# clock.net
KiCad netlist of a schematic drawn in EAGLE
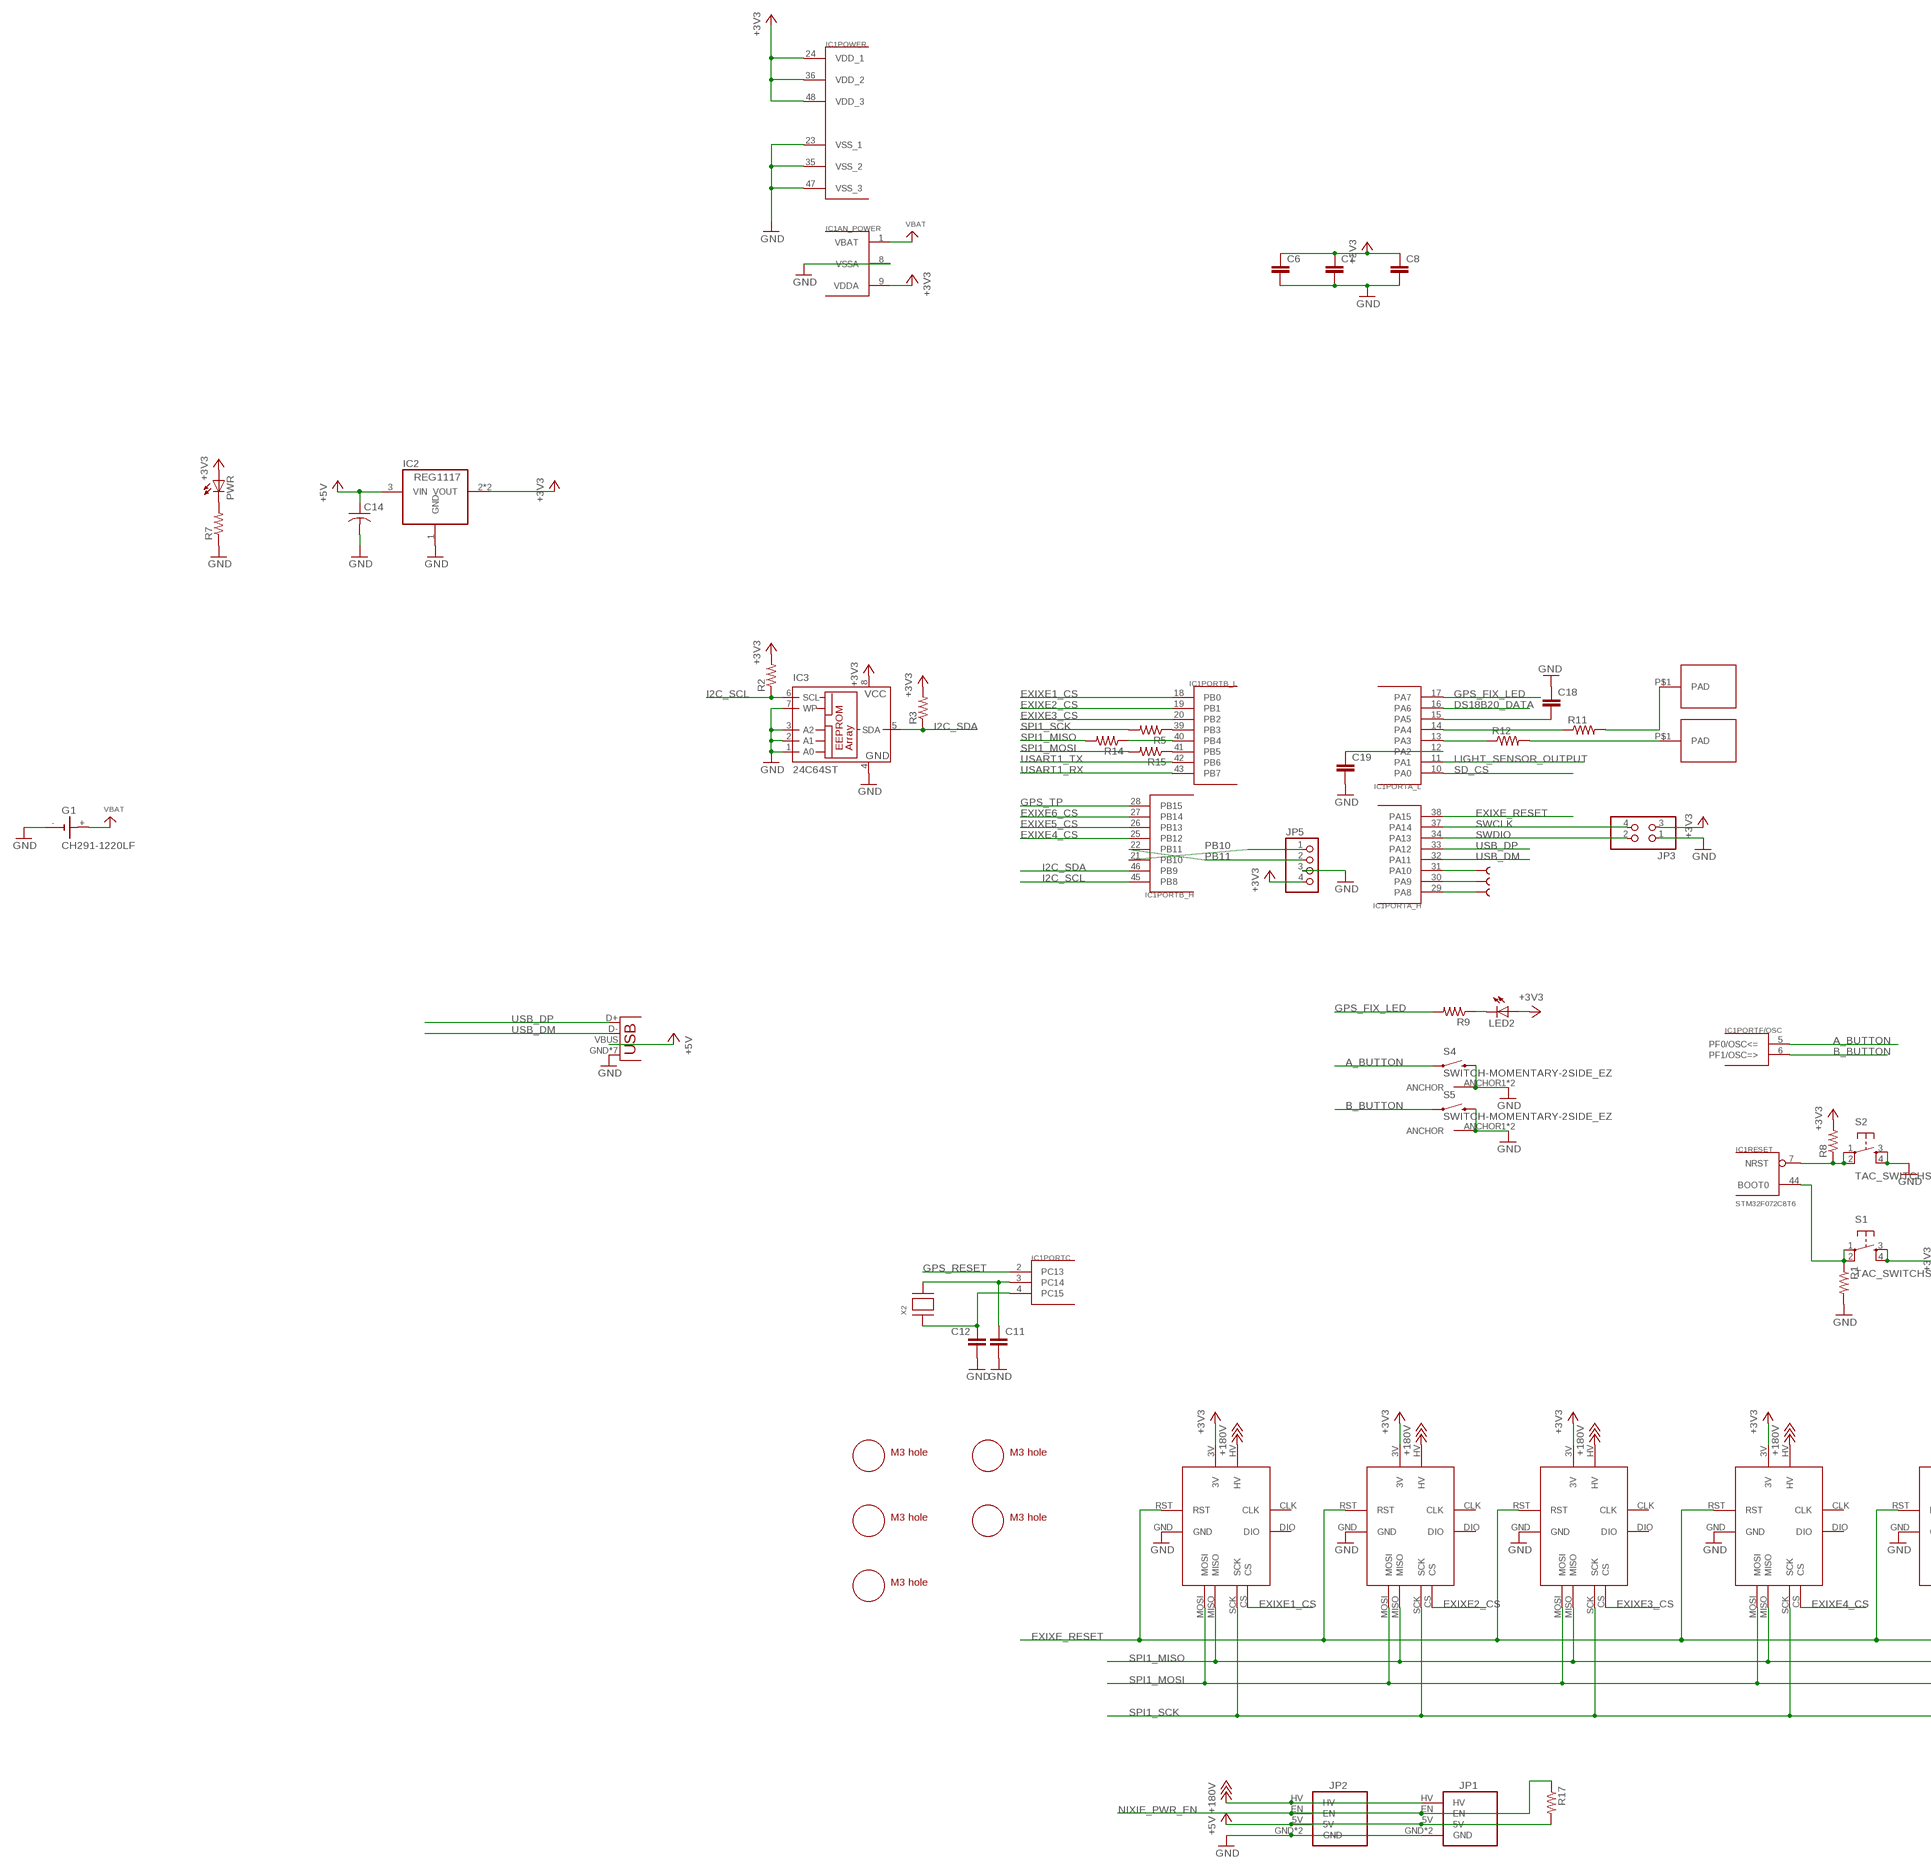
[diagram p0: schematic, sheet 1, part 1 of 2]
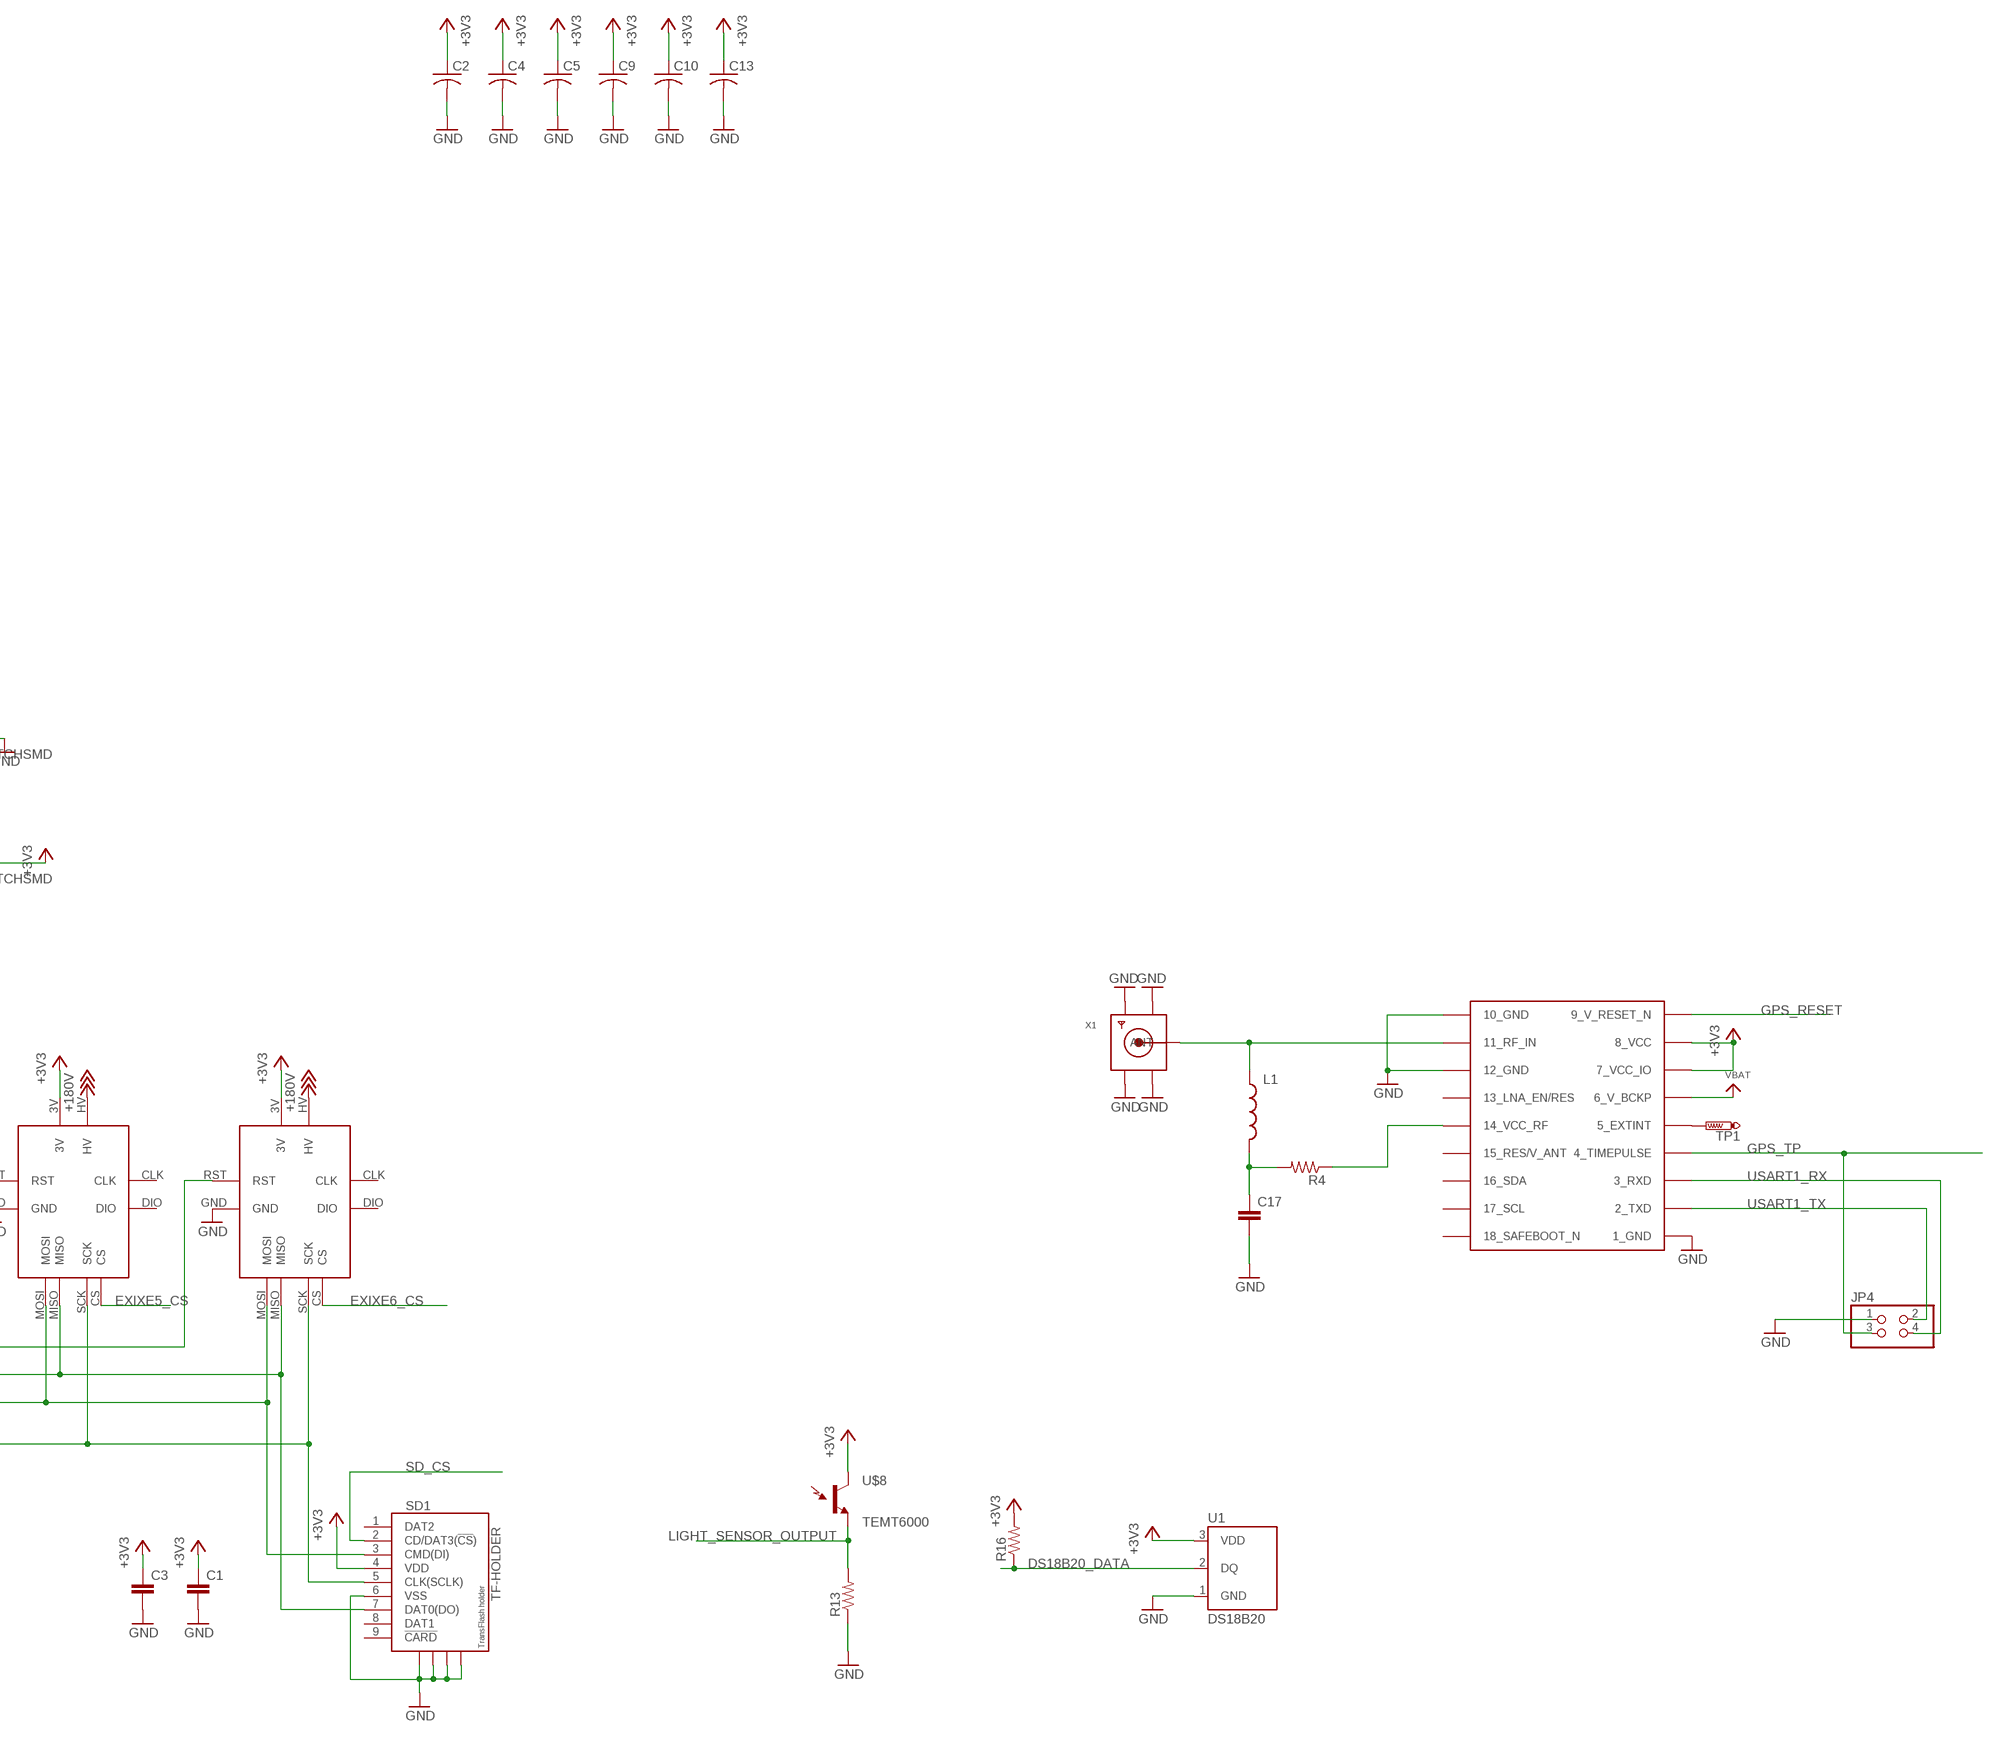
[diagram p1: schematic, sheet 1, part 2 of 2]

(export (version "E")
  (design (tool "Eeschema 10.0.6"))
  (components
    (comp (ref "C1")
      (value "CAP0805")
      (footprint "eagle-import:0805")
      (libsource (lib "eagle-import") (part "CAP0805"))
    )
    (comp (ref "C2")
      (value "C-USC1210")
      (footprint "eagle-import:C1210")
      (libsource (lib "eagle-import") (part "C-USC1210"))
    )
    (comp (ref "C3")
      (value "CAP0805")
      (footprint "eagle-import:0805")
      (libsource (lib "eagle-import") (part "CAP0805"))
    )
    (comp (ref "C4")
      (value "C-USC1210")
      (footprint "eagle-import:C1210")
      (libsource (lib "eagle-import") (part "C-USC1210"))
    )
    (comp (ref "C5")
      (value "C-USC1210")
      (footprint "eagle-import:C1210")
      (libsource (lib "eagle-import") (part "C-USC1210"))
    )
    (comp (ref "C6")
      (value "CAP0805")
      (footprint "eagle-import:0805")
      (libsource (lib "eagle-import") (part "CAP0805"))
    )
    (comp (ref "C7")
      (value "CAP0805")
      (footprint "eagle-import:0805")
      (libsource (lib "eagle-import") (part "CAP0805"))
    )
    (comp (ref "C8")
      (value "CAP0805")
      (footprint "eagle-import:0805")
      (libsource (lib "eagle-import") (part "CAP0805"))
    )
    (comp (ref "C9")
      (value "C-USC1210")
      (footprint "eagle-import:C1210")
      (libsource (lib "eagle-import") (part "C-USC1210"))
    )
    (comp (ref "C10")
      (value "C-USC1210")
      (footprint "eagle-import:C1210")
      (libsource (lib "eagle-import") (part "C-USC1210"))
    )
    (comp (ref "C11")
      (value "CAP0805")
      (footprint "eagle-import:0805")
      (libsource (lib "eagle-import") (part "CAP0805"))
    )
    (comp (ref "C12")
      (value "CAP0805")
      (footprint "eagle-import:0805")
      (libsource (lib "eagle-import") (part "CAP0805"))
    )
    (comp (ref "C13")
      (value "C-USC1210")
      (footprint "eagle-import:C1210")
      (libsource (lib "eagle-import") (part "C-USC1210"))
    )
    (comp (ref "C14")
      (value "C-USC1210")
      (footprint "eagle-import:C1210")
      (libsource (lib "eagle-import") (part "C-USC1210"))
    )
    (comp (ref "C17")
      (value "CAP0805")
      (footprint "eagle-import:0805")
      (libsource (lib "eagle-import") (part "CAP0805"))
    )
    (comp (ref "C18")
      (value "CAP0805")
      (footprint "eagle-import:0805")
      (libsource (lib "eagle-import") (part "CAP0805"))
    )
    (comp (ref "C19")
      (value "CAP0805")
      (footprint "eagle-import:0805")
      (libsource (lib "eagle-import") (part "CAP0805"))
    )
    (comp (ref "G1")
      (value "CH291-1220LF")
      (footprint "eagle-import:CH291-1220LF")
      (libsource (lib "eagle-import") (part "CH291-1220LF"))
    )
    (comp (ref "IC1")
      (value "STM32F072C8T6")
      (footprint "eagle-import:TQFP48")
      (libsource (lib "eagle-import") (part "STM32F072C8T6"))
    )
    (comp (ref "IC2")
      (value "REG1117")
      (footprint "eagle-import:SOT223")
      (libsource (lib "eagle-import") (part "REG1117"))
    )
    (comp (ref "IC3")
      (value "24C64ST")
      (footprint "eagle-import:TSSOP8")
      (fields (field (name "MPN") "CAT24C64YI-GT3"))
      (libsource (lib "eagle-import") (part "24STC64"))
    )
    (comp (ref "JP1")
      (value "EBAY_MODULEEBAY")
      (footprint "eagle-import:EBAY_PKG")
      (libsource (lib "eagle-import") (part "EBAY_MODULEEBAY"))
    )
    (comp (ref "JP2")
      (value "EBAY_MODULETAOBAO")
      (footprint "eagle-import:TAOBAO_PKG")
      (libsource (lib "eagle-import") (part "EBAY_MODULETAOBAO"))
    )
    (comp (ref "JP3")
      (value "PINHD-2X2")
      (footprint "eagle-import:2X02")
      (libsource (lib "eagle-import") (part "PINHD-2X2"))
    )
    (comp (ref "JP4")
      (value "PINHD-2X2")
      (footprint "eagle-import:2X02")
      (libsource (lib "eagle-import") (part "PINHD-2X2"))
    )
    (comp (ref "JP5")
      (value "PINHD-1X4")
      (footprint "eagle-import:1X04")
      (libsource (lib "eagle-import") (part "PINHD-1X4"))
    )
    (comp (ref "L1")
      (value "INDUCTOR0805")
      (footprint "eagle-import:0805")
      (libsource (lib "eagle-import") (part "INDUCTOR0805"))
    )
    (comp (ref "LED2")
      (value "LEDCHIP-LED0805")
      (footprint "eagle-import:CHIP-LED0805")
      (libsource (lib "eagle-import") (part "LEDCHIP-LED0805"))
    )
    (comp (ref "PWR")
      (value "LEDCHIP-LED0805")
      (footprint "eagle-import:CHIP-LED0805")
      (libsource (lib "eagle-import") (part "LEDCHIP-LED0805"))
    )
    (comp (ref "R1")
      (value "RESISTOR0805-RES")
      (footprint "eagle-import:0805")
      (libsource (lib "eagle-import") (part "RESISTOR0805-RES"))
    )
    (comp (ref "R2")
      (value "RESISTOR0805-RES")
      (footprint "eagle-import:0805")
      (libsource (lib "eagle-import") (part "RESISTOR0805-RES"))
    )
    (comp (ref "R3")
      (value "RESISTOR0805-RES")
      (footprint "eagle-import:0805")
      (libsource (lib "eagle-import") (part "RESISTOR0805-RES"))
    )
    (comp (ref "R4")
      (value "RESISTOR0805-RES")
      (footprint "eagle-import:0805")
      (libsource (lib "eagle-import") (part "RESISTOR0805-RES"))
    )
    (comp (ref "R5")
      (value "RESISTOR0805-RES")
      (footprint "eagle-import:0805")
      (libsource (lib "eagle-import") (part "RESISTOR0805-RES"))
    )
    (comp (ref "R7")
      (value "RESISTOR0805-RES")
      (footprint "eagle-import:0805")
      (libsource (lib "eagle-import") (part "RESISTOR0805-RES"))
    )
    (comp (ref "R8")
      (value "RESISTOR0805-RES")
      (footprint "eagle-import:0805")
      (libsource (lib "eagle-import") (part "RESISTOR0805-RES"))
    )
    (comp (ref "R9")
      (value "RESISTOR0805-RES")
      (footprint "eagle-import:0805")
      (libsource (lib "eagle-import") (part "RESISTOR0805-RES"))
    )
    (comp (ref "R11")
      (value "RESISTOR0805-RES")
      (footprint "eagle-import:0805")
      (libsource (lib "eagle-import") (part "RESISTOR0805-RES"))
    )
    (comp (ref "R12")
      (value "RESISTOR0805-RES")
      (footprint "eagle-import:0805")
      (libsource (lib "eagle-import") (part "RESISTOR0805-RES"))
    )
    (comp (ref "R13")
      (value "RESISTOR0805-RES")
      (footprint "eagle-import:0805")
      (libsource (lib "eagle-import") (part "RESISTOR0805-RES"))
    )
    (comp (ref "R14")
      (value "RESISTOR0805-RES")
      (footprint "eagle-import:0805")
      (libsource (lib "eagle-import") (part "RESISTOR0805-RES"))
    )
    (comp (ref "R15")
      (value "RESISTOR0805-RES")
      (footprint "eagle-import:0805")
      (libsource (lib "eagle-import") (part "RESISTOR0805-RES"))
    )
    (comp (ref "R16")
      (value "RESISTOR0805-RES")
      (footprint "eagle-import:0805")
      (libsource (lib "eagle-import") (part "RESISTOR0805-RES"))
    )
    (comp (ref "R17")
      (value "RESISTOR0805-RES")
      (footprint "eagle-import:0805")
      (libsource (lib "eagle-import") (part "RESISTOR0805-RES"))
    )
    (comp (ref "S1")
      (value "TAC_SWITCHSMD")
      (footprint "eagle-import:TACTILE-SWITCH-SMD")
      (libsource (lib "eagle-import") (part "TAC_SWITCHSMD"))
    )
    (comp (ref "S2")
      (value "TAC_SWITCHSMD")
      (footprint "eagle-import:TACTILE-SWITCH-SMD")
      (libsource (lib "eagle-import") (part "TAC_SWITCHSMD"))
    )
    (comp (ref "S4")
      (value "SWITCH-MOMENTARY-2SIDE_EZ")
      (footprint "eagle-import:TACTILE-PTH-SIDEEZ")
      (libsource (lib "eagle-import") (part "SWITCH-MOMENTARY-2SIDE_EZ"))
    )
    (comp (ref "S5")
      (value "SWITCH-MOMENTARY-2SIDE_EZ")
      (footprint "eagle-import:TACTILE-PTH-SIDEEZ")
      (libsource (lib "eagle-import") (part "SWITCH-MOMENTARY-2SIDE_EZ"))
    )
    (comp (ref "SD1")
      (value "TF-HOLDER")
      (footprint "eagle-import:TF-PULL")
      (libsource (lib "eagle-import") (part "TF-HOLDER"))
    )
    (comp (ref "TP1")
      (value "PTR1TP20R")
      (footprint "eagle-import:TP20R")
      (libsource (lib "eagle-import") (part "PTR1TP20R"))
    )
    (comp (ref "TP2")
      (value "TEST-POINT3X5")
      (footprint "eagle-import:PAD.03X.05")
      (libsource (lib "eagle-import") (part "TEST-POINT3X5"))
    )
    (comp (ref "TP3")
      (value "TEST-POINT3X5")
      (footprint "eagle-import:PAD.03X.05")
      (libsource (lib "eagle-import") (part "TEST-POINT3X5"))
    )
    (comp (ref "TP4")
      (value "TEST-POINT3X5")
      (footprint "eagle-import:PAD.03X.05")
      (libsource (lib "eagle-import") (part "TEST-POINT3X5"))
    )
    (comp (ref "U$1")
      (value "EXIXE")
      (footprint "eagle-import:EXIXE_PAC")
      (libsource (lib "eagle-import") (part "EXIXE"))
    )
    (comp (ref "U$2")
      (value "EXIXE")
      (footprint "eagle-import:EXIXE_PAC")
      (libsource (lib "eagle-import") (part "EXIXE"))
    )
    (comp (ref "U$3")
      (value "EXIXE")
      (footprint "eagle-import:EXIXE_PAC")
      (libsource (lib "eagle-import") (part "EXIXE"))
    )
    (comp (ref "U$4")
      (value "EXIXE")
      (footprint "eagle-import:EXIXE_PAC")
      (libsource (lib "eagle-import") (part "EXIXE"))
    )
    (comp (ref "U$5")
      (value "EXIXE")
      (footprint "eagle-import:EXIXE_PAC")
      (libsource (lib "eagle-import") (part "EXIXE"))
    )
    (comp (ref "U$6")
      (value "EXIXE")
      (footprint "eagle-import:EXIXE_PAC")
      (libsource (lib "eagle-import") (part "EXIXE"))
    )
    (comp (ref "U$7")
      (value "MAX-M8")
      (footprint "eagle-import:MAX-M8")
      (libsource (lib "eagle-import") (part "MAX-M8"))
    )
    (comp (ref "U$8")
      (value "TEMT6000")
      (footprint "eagle-import:TEMT6000-SEN")
      (libsource (lib "eagle-import") (part "TEMT6000"))
    )
    (comp (ref "U$10")
      (value "M3_MOUNTING_HOLE")
      (footprint "eagle-import:M3_MOUNTING_HOLE_PACK")
      (libsource (lib "eagle-import") (part "M3_MOUNTING_HOLE"))
    )
    (comp (ref "U$11")
      (value "M3_MOUNTING_HOLE")
      (footprint "eagle-import:M3_MOUNTING_HOLE_PACK")
      (libsource (lib "eagle-import") (part "M3_MOUNTING_HOLE"))
    )
    (comp (ref "U$12")
      (value "M3_MOUNTING_HOLE")
      (footprint "eagle-import:M3_MOUNTING_HOLE_PACK")
      (libsource (lib "eagle-import") (part "M3_MOUNTING_HOLE"))
    )
    (comp (ref "U$13")
      (value "M3_MOUNTING_HOLE")
      (footprint "eagle-import:M3_MOUNTING_HOLE_PACK")
      (libsource (lib "eagle-import") (part "M3_MOUNTING_HOLE"))
    )
    (comp (ref "U$14")
      (value "TOUCHPAD")
      (footprint "eagle-import:TOUCHPAD_PAK")
      (libsource (lib "eagle-import") (part "TOUCHPAD"))
    )
    (comp (ref "U$15")
      (value "TOUCHPAD")
      (footprint "eagle-import:TOUCHPAD_PAK")
      (libsource (lib "eagle-import") (part "TOUCHPAD"))
    )
    (comp (ref "U$20")
      (value "M3_MOUNTING_HOLE")
      (footprint "eagle-import:M3_MOUNTING_HOLE_PACK")
      (libsource (lib "eagle-import") (part "M3_MOUNTING_HOLE"))
    )
    (comp (ref "U1")
      (value "DS18B20")
      (footprint "eagle-import:TO-92-AMMO")
      (libsource (lib "eagle-import") (part "DS18B20"))
    )
    (comp (ref "X1")
      (value "SMACONNECTOR")
      (footprint "eagle-import:SMA90_DIP")
      (libsource (lib "eagle-import") (part "SMACONNECTOR"))
    )
    (comp (ref "X2")
      (value "XTAL-3.2X1.5")
      (footprint "eagle-import:XTAL3215")
      (libsource (lib "eagle-import") (part "XTAL-3.2X1.5"))
    )
    (comp (ref "X3")
      (value "USB-MICROB")
      (footprint "eagle-import:USB-MICROB")
      (libsource (lib "eagle-import") (part "USB-MICROB"))
    )
  )
  (nets
    (net (code "1") (name "+3V3") (class "Default")
      (node (ref "C1") (pin "1") (pinfunction "1_1") (pintype "passive"))
      (node (ref "C10") (pin "1") (pinfunction "1_1") (pintype "passive"))
      (node (ref "C13") (pin "1") (pinfunction "1_1") (pintype "passive"))
      (node (ref "C2") (pin "1") (pinfunction "1_1") (pintype "passive"))
      (node (ref "C3") (pin "1") (pinfunction "1_1") (pintype "passive"))
      (node (ref "C4") (pin "1") (pinfunction "1_1") (pintype "passive"))
      (node (ref "C5") (pin "1") (pinfunction "1_1") (pintype "passive"))
      (node (ref "C6") (pin "1") (pinfunction "1_1") (pintype "passive"))
      (node (ref "C7") (pin "1") (pinfunction "1_1") (pintype "passive"))
      (node (ref "C8") (pin "1") (pinfunction "1_1") (pintype "passive"))
      (node (ref "C9") (pin "1") (pinfunction "1_1") (pintype "passive"))
      (node (ref "IC1") (pin "24") (pinfunction "VDD_1_24") (pintype "power_in"))
      (node (ref "IC1") (pin "36") (pinfunction "VDD_2_36") (pintype "power_in"))
      (node (ref "IC1") (pin "48") (pinfunction "VDD_3_48") (pintype "power_in"))
      (node (ref "IC1") (pin "9") (pinfunction "VDDA_9") (pintype "power_in"))
      (node (ref "IC2") (pin "2") (pinfunction "VOUT_2") (pintype "output"))
      (node (ref "IC2") (pin "4") (pinfunction "VOUT_4") (pintype "output"))
      (node (ref "IC3") (pin "8") (pinfunction "VCC_8") (pintype "power_in"))
      (node (ref "JP3") (pin "3") (pinfunction "3_3") (pintype "passive"))
      (node (ref "JP5") (pin "4") (pinfunction "4_4") (pintype "passive"))
      (node (ref "LED2") (pin "A") (pinfunction "A_A") (pintype "passive"))
      (node (ref "PWR") (pin "A") (pinfunction "A_A") (pintype "passive"))
      (node (ref "R16") (pin "2") (pinfunction "2_2") (pintype "passive"))
      (node (ref "R2") (pin "2") (pinfunction "2_2") (pintype "passive"))
      (node (ref "R3") (pin "2") (pinfunction "2_2") (pintype "passive"))
      (node (ref "R8") (pin "2") (pinfunction "2_2") (pintype "passive"))
      (node (ref "S1") (pin "3") (pinfunction "3_3") (pintype "passive"))
      (node (ref "S1") (pin "4") (pinfunction "4_4") (pintype "passive"))
      (node (ref "SD1") (pin "4") (pinfunction "VDD_4") (pintype "power_in"))
      (node (ref "U$1") (pin "3V") (pinfunction "3V_3V") (pintype "bidirectional"))
      (node (ref "U$2") (pin "3V") (pinfunction "3V_3V") (pintype "bidirectional"))
      (node (ref "U$3") (pin "3V") (pinfunction "3V_3V") (pintype "bidirectional"))
      (node (ref "U$4") (pin "3V") (pinfunction "3V_3V") (pintype "bidirectional"))
      (node (ref "U$5") (pin "3V") (pinfunction "3V_3V") (pintype "bidirectional"))
      (node (ref "U$6") (pin "3V") (pinfunction "3V_3V") (pintype "bidirectional"))
      (node (ref "U$7") (pin "7_VCC_IO") (pinfunction "7_VCC_IO_7_VCC_IO") (pintype "power_in"))
      (node (ref "U$7") (pin "8_VCC") (pinfunction "8_VCC_8_VCC") (pintype "power_in"))
      (node (ref "U$8") (pin "COLLECTOR") (pinfunction "C1_COLLECTOR") (pintype "passive"))
      (node (ref "U1") (pin "3") (pinfunction "VDD_3") (pintype "power_in"))
    )
    (net (code "2") (name "+5V") (class "Default")
      (node (ref "C14") (pin "1") (pinfunction "1_1") (pintype "passive"))
      (node (ref "IC2") (pin "3") (pinfunction "VIN_3") (pintype "input"))
      (node (ref "JP1") (pin "5V") (pinfunction "5V_5V") (pintype "bidirectional"))
      (node (ref "JP2") (pin "5V") (pinfunction "5V_5V") (pintype "bidirectional"))
      (node (ref "R17") (pin "2") (pinfunction "2_2") (pintype "passive"))
      (node (ref "X3") (pin "VBUS") (pinfunction "VBUS_VBUS") (pintype "bidirectional"))
    )
    (net (code "3") (name "+180V") (class "Default")
      (node (ref "JP1") (pin "HV") (pinfunction "HV_HV") (pintype "bidirectional"))
      (node (ref "JP2") (pin "HV") (pinfunction "HV_HV") (pintype "bidirectional"))
      (node (ref "U$1") (pin "HV") (pinfunction "HV_HV") (pintype "bidirectional"))
      (node (ref "U$2") (pin "HV") (pinfunction "HV_HV") (pintype "bidirectional"))
      (node (ref "U$3") (pin "HV") (pinfunction "HV_HV") (pintype "bidirectional"))
      (node (ref "U$4") (pin "HV") (pinfunction "HV_HV") (pintype "bidirectional"))
      (node (ref "U$5") (pin "HV") (pinfunction "HV_HV") (pintype "bidirectional"))
      (node (ref "U$6") (pin "HV") (pinfunction "HV_HV") (pintype "bidirectional"))
    )
    (net (code "4") (name "/A_BUTTON") (class "Default")
      (node (ref "IC1") (pin "5") (pinfunction "PF0/OSC<=_5") (pintype "bidirectional"))
      (node (ref "S4") (pin "1") (pinfunction "1_1") (pintype "passive"))
    )
    (net (code "5") (name "/B_BUTTON") (class "Default")
      (node (ref "IC1") (pin "6") (pinfunction "PF1/OSC=>_6") (pintype "bidirectional"))
      (node (ref "S5") (pin "1") (pinfunction "1_1") (pintype "passive"))
    )
    (net (code "6") (name "/DS18B20_DATA") (class "Default")
      (node (ref "IC1") (pin "16") (pinfunction "PA6_16") (pintype "bidirectional"))
      (node (ref "R16") (pin "1") (pinfunction "1_1") (pintype "passive"))
      (node (ref "U1") (pin "2") (pinfunction "DQ_2") (pintype "bidirectional"))
    )
    (net (code "7") (name "/EXIXE1_CS") (class "Default")
      (node (ref "IC1") (pin "18") (pinfunction "PB0_18") (pintype "bidirectional"))
      (node (ref "U$1") (pin "CS") (pinfunction "CS_CS") (pintype "bidirectional"))
    )
    (net (code "8") (name "/EXIXE2_CS") (class "Default")
      (node (ref "IC1") (pin "19") (pinfunction "PB1_19") (pintype "bidirectional"))
      (node (ref "U$2") (pin "CS") (pinfunction "CS_CS") (pintype "bidirectional"))
    )
    (net (code "9") (name "/EXIXE3_CS") (class "Default")
      (node (ref "IC1") (pin "20") (pinfunction "PB2_20") (pintype "bidirectional"))
      (node (ref "U$3") (pin "CS") (pinfunction "CS_CS") (pintype "bidirectional"))
    )
    (net (code "10") (name "/EXIXE4_CS") (class "Default")
      (node (ref "IC1") (pin "25") (pinfunction "PB12_25") (pintype "bidirectional"))
      (node (ref "U$4") (pin "CS") (pinfunction "CS_CS") (pintype "bidirectional"))
    )
    (net (code "11") (name "/EXIXE5_CS") (class "Default")
      (node (ref "IC1") (pin "26") (pinfunction "PB13_26") (pintype "bidirectional"))
      (node (ref "U$5") (pin "CS") (pinfunction "CS_CS") (pintype "bidirectional"))
    )
    (net (code "12") (name "/EXIXE6_CS") (class "Default")
      (node (ref "IC1") (pin "27") (pinfunction "PB14_27") (pintype "bidirectional"))
      (node (ref "U$6") (pin "CS") (pinfunction "CS_CS") (pintype "bidirectional"))
    )
    (net (code "13") (name "/EXIXE_RESET") (class "Default")
      (node (ref "IC1") (pin "38") (pinfunction "PA15_38") (pintype "bidirectional"))
      (node (ref "U$1") (pin "RST") (pinfunction "RST_RST") (pintype "bidirectional"))
      (node (ref "U$2") (pin "RST") (pinfunction "RST_RST") (pintype "bidirectional"))
      (node (ref "U$3") (pin "RST") (pinfunction "RST_RST") (pintype "bidirectional"))
      (node (ref "U$4") (pin "RST") (pinfunction "RST_RST") (pintype "bidirectional"))
      (node (ref "U$5") (pin "RST") (pinfunction "RST_RST") (pintype "bidirectional"))
      (node (ref "U$6") (pin "RST") (pinfunction "RST_RST") (pintype "bidirectional"))
    )
    (net (code "14") (name "/GPS_FIX_LED") (class "Default")
      (node (ref "IC1") (pin "17") (pinfunction "PA7_17") (pintype "bidirectional"))
      (node (ref "R9") (pin "2") (pinfunction "2_2") (pintype "passive"))
    )
    (net (code "15") (name "/GPS_RESET") (class "Default")
      (node (ref "IC1") (pin "2") (pinfunction "PC13_2") (pintype "bidirectional"))
      (node (ref "U$7") (pin "9_RESET_N") (pinfunction "9_V_RESET_N_9_RESET_N") (pintype "power_in"))
    )
    (net (code "16") (name "/GPS_TP") (class "Default")
      (node (ref "IC1") (pin "28") (pinfunction "PB15_28") (pintype "bidirectional"))
      (node (ref "JP4") (pin "3") (pinfunction "3_3") (pintype "passive"))
      (node (ref "U$7") (pin "4_TIMEPULSE") (pinfunction "4_TIMEPULSE_4_TIMEPULSE") (pintype "bidirectional"))
    )
    (net (code "17") (name "/I2C_SCL") (class "Default")
      (node (ref "IC1") (pin "45") (pinfunction "PB8_45") (pintype "bidirectional"))
      (node (ref "IC3") (pin "6") (pinfunction "SCL_6") (pintype "input"))
      (node (ref "R2") (pin "1") (pinfunction "1_1") (pintype "passive"))
    )
    (net (code "18") (name "/I2C_SDA") (class "Default")
      (node (ref "IC1") (pin "46") (pinfunction "PB9_46") (pintype "bidirectional"))
      (node (ref "IC3") (pin "5") (pinfunction "SDA_5") (pintype "bidirectional"))
      (node (ref "R3") (pin "1") (pinfunction "1_1") (pintype "passive"))
    )
    (net (code "19") (name "/LIGHT_SENSOR_OUTPUT") (class "Default")
      (node (ref "IC1") (pin "11") (pinfunction "PA1_11") (pintype "bidirectional"))
      (node (ref "R13") (pin "2") (pinfunction "2_2") (pintype "passive"))
      (node (ref "U$8") (pin "EMITTER") (pinfunction "E1_EMITTER") (pintype "passive"))
    )
    (net (code "20") (name "/NIXIE_PWR_EN") (class "Default")
      (node (ref "JP1") (pin "EN") (pinfunction "EN_EN") (pintype "bidirectional"))
      (node (ref "JP2") (pin "EN") (pinfunction "EN_EN") (pintype "bidirectional"))
      (node (ref "R17") (pin "1") (pinfunction "1_1") (pintype "passive"))
    )
    (net (code "21") (name "/PB10") (class "Default")
      (node (ref "IC1") (pin "21") (pinfunction "PB10_21") (pintype "bidirectional"))
      (node (ref "JP5") (pin "1") (pinfunction "1_1") (pintype "passive"))
    )
    (net (code "22") (name "/PB11") (class "Default")
      (node (ref "IC1") (pin "22") (pinfunction "PB11_22") (pintype "bidirectional"))
      (node (ref "JP5") (pin "2") (pinfunction "2_2") (pintype "passive"))
    )
    (net (code "23") (name "/SD_CS") (class "Default")
      (node (ref "IC1") (pin "10") (pinfunction "PA0_10") (pintype "bidirectional"))
      (node (ref "SD1") (pin "2") (pinfunction "CD/DAT3(~{CS})_2") (pintype "bidirectional"))
    )
    (net (code "24") (name "/SPI1_MISO") (class "Default")
      (node (ref "R14") (pin "2") (pinfunction "2_2") (pintype "passive"))
      (node (ref "SD1") (pin "7") (pinfunction "DAT0(DO)_7") (pintype "bidirectional"))
      (node (ref "U$1") (pin "MISO") (pinfunction "MISO_MISO") (pintype "bidirectional"))
      (node (ref "U$2") (pin "MISO") (pinfunction "MISO_MISO") (pintype "bidirectional"))
      (node (ref "U$3") (pin "MISO") (pinfunction "MISO_MISO") (pintype "bidirectional"))
      (node (ref "U$4") (pin "MISO") (pinfunction "MISO_MISO") (pintype "bidirectional"))
      (node (ref "U$5") (pin "MISO") (pinfunction "MISO_MISO") (pintype "bidirectional"))
      (node (ref "U$6") (pin "MISO") (pinfunction "MISO_MISO") (pintype "bidirectional"))
    )
    (net (code "25") (name "/SPI1_MOSI") (class "Default")
      (node (ref "R15") (pin "2") (pinfunction "2_2") (pintype "passive"))
      (node (ref "SD1") (pin "3") (pinfunction "CMD(DI)_3") (pintype "bidirectional"))
      (node (ref "U$1") (pin "MOSI") (pinfunction "MOSI_MOSI") (pintype "bidirectional"))
      (node (ref "U$2") (pin "MOSI") (pinfunction "MOSI_MOSI") (pintype "bidirectional"))
      (node (ref "U$3") (pin "MOSI") (pinfunction "MOSI_MOSI") (pintype "bidirectional"))
      (node (ref "U$4") (pin "MOSI") (pinfunction "MOSI_MOSI") (pintype "bidirectional"))
      (node (ref "U$5") (pin "MOSI") (pinfunction "MOSI_MOSI") (pintype "bidirectional"))
      (node (ref "U$6") (pin "MOSI") (pinfunction "MOSI_MOSI") (pintype "bidirectional"))
    )
    (net (code "26") (name "/SPI1_SCK") (class "Default")
      (node (ref "R5") (pin "2") (pinfunction "2_2") (pintype "passive"))
      (node (ref "SD1") (pin "5") (pinfunction "CLK(SCLK)_5") (pintype "input"))
      (node (ref "U$1") (pin "SCK") (pinfunction "SCK_SCK") (pintype "bidirectional"))
      (node (ref "U$2") (pin "SCK") (pinfunction "SCK_SCK") (pintype "bidirectional"))
      (node (ref "U$3") (pin "SCK") (pinfunction "SCK_SCK") (pintype "bidirectional"))
      (node (ref "U$4") (pin "SCK") (pinfunction "SCK_SCK") (pintype "bidirectional"))
      (node (ref "U$5") (pin "SCK") (pinfunction "SCK_SCK") (pintype "bidirectional"))
      (node (ref "U$6") (pin "SCK") (pinfunction "SCK_SCK") (pintype "bidirectional"))
    )
    (net (code "27") (name "/SWCLK") (class "Default")
      (node (ref "IC1") (pin "37") (pinfunction "PA14_37") (pintype "bidirectional"))
      (node (ref "JP3") (pin "4") (pinfunction "4_4") (pintype "passive"))
    )
    (net (code "28") (name "/SWDIO") (class "Default")
      (node (ref "IC1") (pin "34") (pinfunction "PA13_34") (pintype "bidirectional"))
      (node (ref "JP3") (pin "2") (pinfunction "2_2") (pintype "passive"))
    )
    (net (code "29") (name "/USART1_RX") (class "Default")
      (node (ref "IC1") (pin "43") (pinfunction "PB7_43") (pintype "bidirectional"))
      (node (ref "JP4") (pin "4") (pinfunction "4_4") (pintype "passive"))
      (node (ref "U$7") (pin "3_RXD") (pinfunction "3_RXD_3_RXD") (pintype "bidirectional"))
    )
    (net (code "30") (name "/USART1_TX") (class "Default")
      (node (ref "IC1") (pin "42") (pinfunction "PB6_42") (pintype "bidirectional"))
      (node (ref "JP4") (pin "2") (pinfunction "2_2") (pintype "passive"))
      (node (ref "U$7") (pin "2_TXD") (pinfunction "2_TXD_2_TXD") (pintype "bidirectional"))
    )
    (net (code "31") (name "/USB_DM") (class "Default")
      (node (ref "IC1") (pin "32") (pinfunction "PA11_32") (pintype "bidirectional"))
      (node (ref "X3") (pin "D-") (pinfunction "D-_D-") (pintype "bidirectional"))
    )
    (net (code "32") (name "/USB_DP") (class "Default")
      (node (ref "IC1") (pin "33") (pinfunction "PA12_33") (pintype "bidirectional"))
      (node (ref "X3") (pin "D+") (pinfunction "D+_D+") (pintype "bidirectional"))
    )
    (net (code "33") (name "GND") (class "Default")
      (node (ref "C1") (pin "2") (pinfunction "2_2") (pintype "passive"))
      (node (ref "C10") (pin "2") (pinfunction "2_2") (pintype "passive"))
      (node (ref "C11") (pin "2") (pinfunction "2_2") (pintype "passive"))
      (node (ref "C12") (pin "2") (pinfunction "2_2") (pintype "passive"))
      (node (ref "C13") (pin "2") (pinfunction "2_2") (pintype "passive"))
      (node (ref "C14") (pin "2") (pinfunction "2_2") (pintype "passive"))
      (node (ref "C17") (pin "2") (pinfunction "2_2") (pintype "passive"))
      (node (ref "C18") (pin "1") (pinfunction "1_1") (pintype "passive"))
      (node (ref "C19") (pin "2") (pinfunction "2_2") (pintype "passive"))
      (node (ref "C2") (pin "2") (pinfunction "2_2") (pintype "passive"))
      (node (ref "C3") (pin "2") (pinfunction "2_2") (pintype "passive"))
      (node (ref "C4") (pin "2") (pinfunction "2_2") (pintype "passive"))
      (node (ref "C5") (pin "2") (pinfunction "2_2") (pintype "passive"))
      (node (ref "C6") (pin "2") (pinfunction "2_2") (pintype "passive"))
      (node (ref "C7") (pin "2") (pinfunction "2_2") (pintype "passive"))
      (node (ref "C8") (pin "2") (pinfunction "2_2") (pintype "passive"))
      (node (ref "C9") (pin "2") (pinfunction "2_2") (pintype "passive"))
      (node (ref "G1") (pin "-") (pinfunction "-_-") (pintype "passive"))
      (node (ref "IC1") (pin "23") (pinfunction "VSS_1_23") (pintype "power_in"))
      (node (ref "IC1") (pin "35") (pinfunction "VSS_2_35") (pintype "power_in"))
      (node (ref "IC1") (pin "47") (pinfunction "VSS_3_47") (pintype "power_in"))
      (node (ref "IC1") (pin "8") (pinfunction "VSSA_8") (pintype "power_in"))
      (node (ref "IC2") (pin "1") (pinfunction "GND_1") (pintype "power_in"))
      (node (ref "IC3") (pin "1") (pinfunction "A0_1") (pintype "input"))
      (node (ref "IC3") (pin "2") (pinfunction "A1_2") (pintype "input"))
      (node (ref "IC3") (pin "3") (pinfunction "A2_3") (pintype "input"))
      (node (ref "IC3") (pin "4") (pinfunction "GND_4") (pintype "power_in"))
      (node (ref "IC3") (pin "7") (pinfunction "WP_7") (pintype "input"))
      (node (ref "JP1") (pin "GND") (pinfunction "GND_GND") (pintype "bidirectional"))
      (node (ref "JP1") (pin "GND2") (pinfunction "GND_GND2") (pintype "bidirectional"))
      (node (ref "JP2") (pin "GND") (pinfunction "GND_GND") (pintype "bidirectional"))
      (node (ref "JP2") (pin "GND2") (pinfunction "GND_GND2") (pintype "bidirectional"))
      (node (ref "JP3") (pin "1") (pinfunction "1_1") (pintype "passive"))
      (node (ref "JP4") (pin "1") (pinfunction "1_1") (pintype "passive"))
      (node (ref "JP5") (pin "3") (pinfunction "3_3") (pintype "passive"))
      (node (ref "R1") (pin "2") (pinfunction "2_2") (pintype "passive"))
      (node (ref "R13") (pin "1") (pinfunction "1_1") (pintype "passive"))
      (node (ref "R7") (pin "1") (pinfunction "1_1") (pintype "passive"))
      (node (ref "S2") (pin "3") (pinfunction "3_3") (pintype "passive"))
      (node (ref "S2") (pin "4") (pinfunction "4_4") (pintype "passive"))
      (node (ref "S4") (pin "2") (pinfunction "2_2") (pintype "passive"))
      (node (ref "S4") (pin "ANCHOR1") (pinfunction "ANCHOR_ANCHOR1") (pintype "bidirectional"))
      (node (ref "S4") (pin "ANCHOR2") (pinfunction "ANCHOR_ANCHOR2") (pintype "bidirectional"))
      (node (ref "S5") (pin "2") (pinfunction "2_2") (pintype "passive"))
      (node (ref "S5") (pin "ANCHOR1") (pinfunction "ANCHOR_ANCHOR1") (pintype "bidirectional"))
      (node (ref "S5") (pin "ANCHOR2") (pinfunction "ANCHOR_ANCHOR2") (pintype "bidirectional"))
      (node (ref "SD1") (pin "6") (pinfunction "VSS_6") (pintype "power_in"))
      (node (ref "SD1") (pin "S1") (pinfunction "S1_S1") (pintype "passive"))
      (node (ref "SD1") (pin "S2") (pinfunction "S2_S2") (pintype "passive"))
      (node (ref "SD1") (pin "S3") (pinfunction "S3_S3") (pintype "passive"))
      (node (ref "SD1") (pin "S4") (pinfunction "S4_S4") (pintype "passive"))
      (node (ref "U$1") (pin "GND") (pinfunction "GND_GND") (pintype "bidirectional"))
      (node (ref "U$2") (pin "GND") (pinfunction "GND_GND") (pintype "bidirectional"))
      (node (ref "U$3") (pin "GND") (pinfunction "GND_GND") (pintype "bidirectional"))
      (node (ref "U$4") (pin "GND") (pinfunction "GND_GND") (pintype "bidirectional"))
      (node (ref "U$5") (pin "GND") (pinfunction "GND_GND") (pintype "bidirectional"))
      (node (ref "U$6") (pin "GND") (pinfunction "GND_GND") (pintype "bidirectional"))
      (node (ref "U$7") (pin "10_GND") (pinfunction "10_GND_10_GND") (pintype "power_in"))
      (node (ref "U$7") (pin "12_GND") (pinfunction "12_GND_12_GND") (pintype "power_in"))
      (node (ref "U$7") (pin "1_GND") (pinfunction "1_GND_1_GND") (pintype "power_in"))
      (node (ref "U1") (pin "1") (pinfunction "GND_1") (pintype "power_in"))
      (node (ref "X1") (pin "GND1") (pinfunction "GND1_GND1") (pintype "power_in"))
      (node (ref "X1") (pin "GND2") (pinfunction "GND2_GND2") (pintype "power_in"))
      (node (ref "X1") (pin "GND3") (pinfunction "GND3_GND3") (pintype "power_in"))
      (node (ref "X1") (pin "GND4") (pinfunction "GND4_GND4") (pintype "power_in"))
      (node (ref "X3") (pin "GND") (pinfunction "GND_GND") (pintype "bidirectional"))
      (node (ref "X3") (pin "P1") (pinfunction "GND_P1") (pintype "bidirectional"))
      (node (ref "X3") (pin "P2") (pinfunction "GND_P2") (pintype "bidirectional"))
      (node (ref "X3") (pin "P3") (pinfunction "GND_P3") (pintype "bidirectional"))
      (node (ref "X3") (pin "P4") (pinfunction "GND_P4") (pintype "bidirectional"))
      (node (ref "X3") (pin "P5") (pinfunction "GND_P5") (pintype "bidirectional"))
      (node (ref "X3") (pin "P6") (pinfunction "GND_P6") (pintype "bidirectional"))
    )
    (net (code "34") (name "Net-(C17-Pad1)") (class "Default")
      (node (ref "C17") (pin "1") (pinfunction "1_1") (pintype "passive"))
      (node (ref "L1") (pin "2") (pinfunction "2_2") (pintype "passive"))
      (node (ref "R4") (pin "2") (pinfunction "2_2") (pintype "passive"))
    )
    (net (code "35") (name "Net-(IC1B-PA8)") (class "Default")
      (node (ref "IC1") (pin "29") (pinfunction "PA8_29") (pintype "bidirectional"))
      (node (ref "TP4") (pin "P$1") (pinfunction "1_P$1") (pintype "bidirectional"))
    )
    (net (code "36") (name "Net-(IC1B-PA9)") (class "Default")
      (node (ref "IC1") (pin "30") (pinfunction "PA9_30") (pintype "bidirectional"))
      (node (ref "TP3") (pin "P$1") (pinfunction "1_P$1") (pintype "bidirectional"))
    )
    (net (code "37") (name "Net-(IC1B-PA10)") (class "Default")
      (node (ref "IC1") (pin "31") (pinfunction "PA10_31") (pintype "bidirectional"))
      (node (ref "TP2") (pin "P$1") (pinfunction "1_P$1") (pintype "bidirectional"))
    )
    (net (code "38") (name "Net-(IC1C-PA2)") (class "Default")
      (node (ref "C19") (pin "1") (pinfunction "1_1") (pintype "passive"))
      (node (ref "IC1") (pin "12") (pinfunction "PA2_12") (pintype "bidirectional"))
    )
    (net (code "39") (name "Net-(IC1C-PA3)") (class "Default")
      (node (ref "IC1") (pin "13") (pinfunction "PA3_13") (pintype "bidirectional"))
      (node (ref "R12") (pin "1") (pinfunction "1_1") (pintype "passive"))
    )
    (net (code "40") (name "Net-(IC1C-PA4)") (class "Default")
      (node (ref "IC1") (pin "14") (pinfunction "PA4_14") (pintype "bidirectional"))
      (node (ref "R11") (pin "1") (pinfunction "1_1") (pintype "passive"))
    )
    (net (code "41") (name "Net-(IC1C-PA5)") (class "Default")
      (node (ref "C18") (pin "2") (pinfunction "2_2") (pintype "passive"))
      (node (ref "IC1") (pin "15") (pinfunction "PA5_15") (pintype "bidirectional"))
    )
    (net (code "42") (name "Net-(IC1E-PB3)") (class "Default")
      (node (ref "IC1") (pin "39") (pinfunction "PB3_39") (pintype "bidirectional"))
      (node (ref "R5") (pin "1") (pinfunction "1_1") (pintype "passive"))
    )
    (net (code "43") (name "Net-(IC1E-PB4)") (class "Default")
      (node (ref "IC1") (pin "40") (pinfunction "PB4_40") (pintype "bidirectional"))
      (node (ref "R14") (pin "1") (pinfunction "1_1") (pintype "passive"))
    )
    (net (code "44") (name "Net-(IC1E-PB5)") (class "Default")
      (node (ref "IC1") (pin "41") (pinfunction "PB5_41") (pintype "bidirectional"))
      (node (ref "R15") (pin "1") (pinfunction "1_1") (pintype "passive"))
    )
    (net (code "45") (name "Net-(IC1F-PC14)") (class "Default")
      (node (ref "C11") (pin "1") (pinfunction "1_1") (pintype "passive"))
      (node (ref "IC1") (pin "3") (pinfunction "PC14_3") (pintype "bidirectional"))
      (node (ref "X2") (pin "P$2") (pinfunction "P$2_P$2") (pintype "bidirectional"))
    )
    (net (code "46") (name "Net-(IC1F-PC15)") (class "Default")
      (node (ref "C12") (pin "1") (pinfunction "1_1") (pintype "passive"))
      (node (ref "IC1") (pin "4") (pinfunction "PC15_4") (pintype "bidirectional"))
      (node (ref "X2") (pin "P$1") (pinfunction "P$1_P$1") (pintype "bidirectional"))
    )
    (net (code "47") (name "Net-(IC1I-BOOT0)") (class "Default")
      (node (ref "IC1") (pin "44") (pinfunction "BOOT0_44") (pintype "input"))
      (node (ref "R1") (pin "1") (pinfunction "1_1") (pintype "passive"))
      (node (ref "S1") (pin "1") (pinfunction "1_1") (pintype "passive"))
      (node (ref "S1") (pin "2") (pinfunction "2_2") (pintype "passive"))
    )
    (net (code "48") (name "Net-(IC1I-NRST)") (class "Default")
      (node (ref "IC1") (pin "7") (pinfunction "NRST_7") (pintype "input"))
      (node (ref "R8") (pin "1") (pinfunction "1_1") (pintype "passive"))
      (node (ref "S2") (pin "1") (pinfunction "1_1") (pintype "passive"))
      (node (ref "S2") (pin "2") (pinfunction "2_2") (pintype "passive"))
    )
    (net (code "49") (name "Net-(LED2-PadC)") (class "Default")
      (node (ref "LED2") (pin "C") (pinfunction "C_C") (pintype "passive"))
      (node (ref "R9") (pin "1") (pinfunction "1_1") (pintype "passive"))
    )
    (net (code "50") (name "Net-(PWR-PadC)") (class "Default")
      (node (ref "PWR") (pin "C") (pinfunction "C_C") (pintype "passive"))
      (node (ref "R7") (pin "2") (pinfunction "2_2") (pintype "passive"))
    )
    (net (code "51") (name "Net-(R4-Pad1)") (class "Default")
      (node (ref "R4") (pin "1") (pinfunction "1_1") (pintype "passive"))
      (node (ref "U$7") (pin "14_VCC_RF") (pinfunction "14_VCC_RF_14_VCC_RF") (pintype "bidirectional"))
    )
    (net (code "52") (name "Net-(TP1-PadTP)") (class "Default")
      (node (ref "TP1") (pin "TP") (pinfunction "TP_TP") (pintype "input"))
      (node (ref "U$7") (pin "5_EXTINT") (pinfunction "5_EXTINT_5_EXTINT") (pintype "bidirectional"))
    )
    (net (code "53") (name "Net-(U$14-PAD)") (class "Default")
      (node (ref "R12") (pin "2") (pinfunction "2_2") (pintype "passive"))
      (node (ref "U$14") (pin "P$1") (pinfunction "PAD_P$1") (pintype "bidirectional"))
    )
    (net (code "54") (name "Net-(U$15-PAD)") (class "Default")
      (node (ref "R11") (pin "2") (pinfunction "2_2") (pintype "passive"))
      (node (ref "U$15") (pin "P$1") (pinfunction "PAD_P$1") (pintype "bidirectional"))
    )
    (net (code "55") (name "Net-(X1-ANT)") (class "Default")
      (node (ref "L1") (pin "1") (pinfunction "1_1") (pintype "passive"))
      (node (ref "U$7") (pin "11_RF_IN") (pinfunction "11_RF_IN_11_RF_IN") (pintype "bidirectional"))
      (node (ref "X1") (pin "ANTENNA") (pinfunction "ANT_ANTENNA") (pintype "bidirectional"))
    )
    (net (code "56") (name "VBAT") (class "Default")
      (node (ref "G1") (pin "+") (pinfunction "+_+") (pintype "passive"))
      (node (ref "IC1") (pin "1") (pinfunction "VBAT_1") (pintype "power_in"))
      (node (ref "U$7") (pin "6_V_BCKP") (pinfunction "6_V_BCKP_6_V_BCKP") (pintype "bidirectional"))
    )
    (net (code "57") (name "unconnected-(SD1-DAT1-Pad8)") (class "Default")
      (node (ref "SD1") (pin "8") (pinfunction "DAT1_8") (pintype "bidirectional"))
    )
    (net (code "58") (name "unconnected-(SD1-DAT2-Pad1)") (class "Default")
      (node (ref "SD1") (pin "1") (pinfunction "DAT2_1") (pintype "bidirectional"))
    )
    (net (code "59") (name "unconnected-(SD1-~{CARD}-Pad9)") (class "Default")
      (node (ref "SD1") (pin "9") (pinfunction "~{CARD}_9") (pintype "passive"))
    )
    (net (code "60") (name "unconnected-(U$1-PadCLK)") (class "Default")
      (node (ref "U$1") (pin "CLK") (pinfunction "CLK_CLK") (pintype "bidirectional"))
    )
    (net (code "61") (name "unconnected-(U$1-PadDIO)") (class "Default")
      (node (ref "U$1") (pin "DIO") (pinfunction "DIO_DIO") (pintype "bidirectional"))
    )
    (net (code "62") (name "unconnected-(U$2-PadCLK)") (class "Default")
      (node (ref "U$2") (pin "CLK") (pinfunction "CLK_CLK") (pintype "bidirectional"))
    )
    (net (code "63") (name "unconnected-(U$2-PadDIO)") (class "Default")
      (node (ref "U$2") (pin "DIO") (pinfunction "DIO_DIO") (pintype "bidirectional"))
    )
    (net (code "64") (name "unconnected-(U$3-PadCLK)") (class "Default")
      (node (ref "U$3") (pin "CLK") (pinfunction "CLK_CLK") (pintype "bidirectional"))
    )
    (net (code "65") (name "unconnected-(U$3-PadDIO)") (class "Default")
      (node (ref "U$3") (pin "DIO") (pinfunction "DIO_DIO") (pintype "bidirectional"))
    )
    (net (code "66") (name "unconnected-(U$4-PadCLK)") (class "Default")
      (node (ref "U$4") (pin "CLK") (pinfunction "CLK_CLK") (pintype "bidirectional"))
    )
    (net (code "67") (name "unconnected-(U$4-PadDIO)") (class "Default")
      (node (ref "U$4") (pin "DIO") (pinfunction "DIO_DIO") (pintype "bidirectional"))
    )
    (net (code "68") (name "unconnected-(U$5-PadCLK)") (class "Default")
      (node (ref "U$5") (pin "CLK") (pinfunction "CLK_CLK") (pintype "bidirectional"))
    )
    (net (code "69") (name "unconnected-(U$5-PadDIO)") (class "Default")
      (node (ref "U$5") (pin "DIO") (pinfunction "DIO_DIO") (pintype "bidirectional"))
    )
    (net (code "70") (name "unconnected-(U$6-PadCLK)") (class "Default")
      (node (ref "U$6") (pin "CLK") (pinfunction "CLK_CLK") (pintype "bidirectional"))
    )
    (net (code "71") (name "unconnected-(U$6-PadDIO)") (class "Default")
      (node (ref "U$6") (pin "DIO") (pinfunction "DIO_DIO") (pintype "bidirectional"))
    )
    (net (code "72") (name "unconnected-(U$7-13_LNA_EN{slash}RES-Pad13_LNA_EN)") (class "Default")
      (node (ref "U$7") (pin "13_LNA_EN") (pinfunction "13_LNA_EN/RES_13_LNA_EN") (pintype "bidirectional"))
    )
    (net (code "73") (name "unconnected-(U$7-15_RES{slash}V_ANT-Pad15_V_ANT{slash}RESERVED)") (class "Default")
      (node (ref "U$7") (pin "15_V_ANT/RESERVED") (pinfunction "15_RES/V_ANT_15_V_ANT/RESERVED") (pintype "bidirectional"))
    )
    (net (code "74") (name "unconnected-(U$7-Pad16_SDA)") (class "Default")
      (node (ref "U$7") (pin "16_SDA") (pinfunction "16_SDA_16_SDA") (pintype "bidirectional"))
    )
    (net (code "75") (name "unconnected-(U$7-Pad17_SCL)") (class "Default")
      (node (ref "U$7") (pin "17_SCL") (pinfunction "17_SCL_17_SCL") (pintype "bidirectional"))
    )
    (net (code "76") (name "unconnected-(U$7-Pad18_SAFEBOOT_N)") (class "Default")
      (node (ref "U$7") (pin "18_SAFEBOOT_N") (pinfunction "18_SAFEBOOT_N_18_SAFEBOOT_N") (pintype "bidirectional"))
    )
  )
)
